# lcd_key_led.net
KiCad netlist of a schematic drawn in Altium Designer
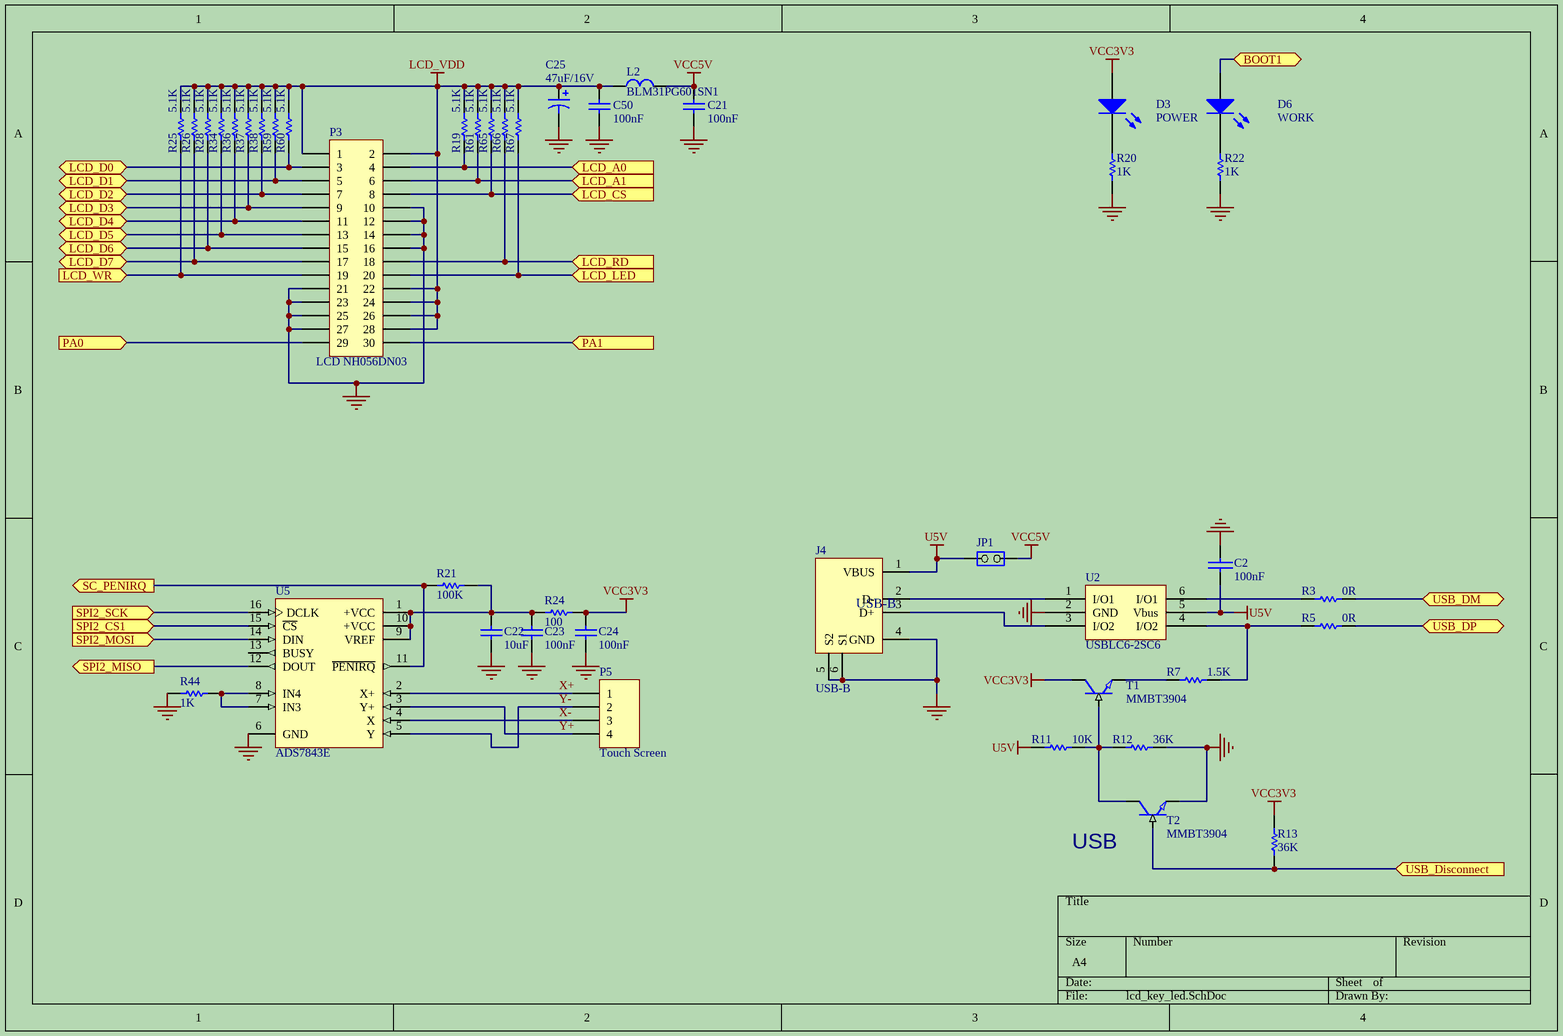
[diagram p0: lcd_key_led.SchDoc]

(export (version "E")
  (design (tool "Eeschema 10.0.6"))
  (components
    (comp (ref "C2")
      (value "100nF")
      (footprint "C0805")
      (description "Capacitor")
      (libsource (lib "*") (part "CAP"))
    )
    (comp (ref "C21")
      (value "100nF")
      (footprint "C0805")
      (description "Capacitor")
      (fields (field (name "PUBLISHER") "Altium Limited"))
      (libsource (lib "Miscellaneous Devices") (part "CAP"))
    )
    (comp (ref "C22")
      (value "10uF")
      (footprint "C1206")
      (description "Capacitor")
      (fields (field (name "PUBLISHER") "Altium Limited"))
      (libsource (lib "Miscellaneous Devices") (part "CAP"))
    )
    (comp (ref "C23")
      (value "100nF")
      (footprint "C0805")
      (description "Capacitor")
      (fields (field (name "PUBLISHER") "Altium Limited"))
      (libsource (lib "Miscellaneous Devices") (part "CAP"))
    )
    (comp (ref "C24")
      (value "100nF")
      (footprint "C0805")
      (description "Capacitor")
      (fields (field (name "PUBLISHER") "Altium Limited"))
      (libsource (lib "Miscellaneous Devices") (part "CAP"))
    )
    (comp (ref "C25")
      (value "47uF/16V")
      (footprint "CD1/2")
      (description "Polarized Capacitor (Radial)")
      (fields (field (name "PUBLISHER") "Altium Limited"))
      (libsource (lib "Miscellaneous Devices") (part "Cap Pol1"))
    )
    (comp (ref "C50")
      (value "100nF")
      (footprint "C0805")
      (description "Capacitor")
      (fields (field (name "PUBLISHER") "Altium Limited"))
      (libsource (lib "Miscellaneous Devices") (part "CAP"))
    )
    (comp (ref "D3")
      (value "POWER")
      (footprint "LED0805")
      (description "Typical INFRARED GaAs LED")
      (fields (field (name "PUBLISHER") "Altium Limited"))
      (libsource (lib "Miscellaneous Devices") (part "LED0"))
    )
    (comp (ref "D6")
      (value "WORK")
      (footprint "LED0805")
      (description "Typical INFRARED GaAs LED")
      (fields (field (name "PUBLISHER") "Altium Limited"))
      (libsource (lib "Miscellaneous Devices") (part "LED0"))
    )
    (comp (ref "J4") (value "USB-B") (footprint "USB-B") (libsource (lib "Devices") (part "USB-B")))
    (comp (ref "JP1") (value "~") (footprint "SIP2") (libsource (lib "*") (part "JP2")))
    (comp (ref "L2") (value "BLM31PG601SN1") (footprint "l1206") (libsource (lib "Devices") (part "L1")))
    (comp (ref "P3")
      (value "LCD NH056DN03")
      (footprint "HDR2X15")
      (description "Header, 15-Pin, Dual row")
      (fields (field (name "PUBLISHER") "Altium Limited"))
      (libsource (lib "Miscellaneous Connectors") (part "Header 15X2"))
    )
    (comp (ref "P5")
      (value "Touch Screen")
      (footprint "TJC3-4A")
      (description "Header, 4-Pin")
      (fields (field (name "PUBLISHER") "Altium Limited"))
      (libsource (lib "Miscellaneous Connectors") (part "Header 4"))
    )
    (comp (ref "R3")
      (value "0R")
      (footprint "R0805")
      (description "Resistor")
      (fields (field (name "PUBLISHER") "Altium Limited"))
      (libsource (lib "") (part "Res1_1"))
    )
    (comp (ref "R5")
      (value "0R")
      (footprint "R0805")
      (description "Resistor")
      (fields (field (name "PUBLISHER") "Altium Limited"))
      (libsource (lib "") (part "Res1_1"))
    )
    (comp (ref "R7")
      (value "1.5K")
      (footprint "R0805")
      (description "Resistor")
      (fields (field (name "PUBLISHER") "Altium Limited"))
      (libsource (lib "") (part "Res1_1"))
    )
    (comp (ref "R11")
      (value "10K")
      (footprint "R0805")
      (description "Resistor")
      (fields (field (name "PUBLISHER") "Altium Limited"))
      (libsource (lib "") (part "Res1_1"))
    )
    (comp (ref "R12")
      (value "36K")
      (footprint "R0805")
      (description "Resistor")
      (fields (field (name "PUBLISHER") "Altium Limited"))
      (libsource (lib "") (part "Res1_1"))
    )
    (comp (ref "R13")
      (value "36K")
      (footprint "R0805")
      (description "Resistor")
      (fields (field (name "PUBLISHER") "Altium Limited"))
      (libsource (lib "") (part "Res1_1"))
    )
    (comp (ref "R19")
      (value "5.1K")
      (footprint "R0805")
      (description "Resistor")
      (fields (field (name "PUBLISHER") "Altium Limited"))
      (libsource (lib "Miscellaneous Devices") (part "Res1"))
    )
    (comp (ref "R20")
      (value "1K")
      (footprint "R0805")
      (description "Resistor")
      (fields (field (name "PUBLISHER") "Altium Limited"))
      (libsource (lib "Miscellaneous Devices") (part "Res1"))
    )
    (comp (ref "R21")
      (value "100K")
      (footprint "R0805")
      (description "Resistor")
      (fields (field (name "PUBLISHER") "Altium Limited"))
      (libsource (lib "Miscellaneous Devices") (part "Res1"))
    )
    (comp (ref "R22")
      (value "1K")
      (footprint "R0805")
      (description "Resistor")
      (fields (field (name "PUBLISHER") "Altium Limited"))
      (libsource (lib "Miscellaneous Devices") (part "Res1"))
    )
    (comp (ref "R24")
      (value "100")
      (footprint "R0805")
      (description "Resistor")
      (fields (field (name "PUBLISHER") "Altium Limited"))
      (libsource (lib "Miscellaneous Devices") (part "Res1"))
    )
    (comp (ref "R25")
      (value "5.1K")
      (footprint "R0805")
      (description "Resistor")
      (fields (field (name "PUBLISHER") "Altium Limited"))
      (libsource (lib "Miscellaneous Devices") (part "Res1"))
    )
    (comp (ref "R26")
      (value "5.1K")
      (footprint "R0805")
      (description "Resistor")
      (fields (field (name "PUBLISHER") "Altium Limited"))
      (libsource (lib "Miscellaneous Devices") (part "Res1"))
    )
    (comp (ref "R28")
      (value "5.1K")
      (footprint "R0805")
      (description "Resistor")
      (fields (field (name "PUBLISHER") "Altium Limited"))
      (libsource (lib "Miscellaneous Devices") (part "Res1"))
    )
    (comp (ref "R34")
      (value "5.1K")
      (footprint "R0805")
      (description "Resistor")
      (fields (field (name "PUBLISHER") "Altium Limited"))
      (libsource (lib "Miscellaneous Devices") (part "Res1"))
    )
    (comp (ref "R36")
      (value "5.1K")
      (footprint "R0805")
      (description "Resistor")
      (fields (field (name "PUBLISHER") "Altium Limited"))
      (libsource (lib "Miscellaneous Devices") (part "Res1"))
    )
    (comp (ref "R37")
      (value "5.1K")
      (footprint "R0805")
      (description "Resistor")
      (fields (field (name "PUBLISHER") "Altium Limited"))
      (libsource (lib "Miscellaneous Devices") (part "Res1"))
    )
    (comp (ref "R38")
      (value "5.1K")
      (footprint "R0805")
      (description "Resistor")
      (fields (field (name "PUBLISHER") "Altium Limited"))
      (libsource (lib "Miscellaneous Devices") (part "Res1"))
    )
    (comp (ref "R44")
      (value "1K")
      (footprint "R0805")
      (description "Resistor")
      (fields (field (name "PUBLISHER") "Altium Limited"))
      (libsource (lib "Miscellaneous Devices") (part "Res1"))
    )
    (comp (ref "R59")
      (value "5.1K")
      (footprint "R0805")
      (description "Resistor")
      (fields (field (name "PUBLISHER") "Altium Limited"))
      (libsource (lib "Miscellaneous Devices") (part "Res1"))
    )
    (comp (ref "R60")
      (value "5.1K")
      (footprint "R0805")
      (description "Resistor")
      (fields (field (name "PUBLISHER") "Altium Limited"))
      (libsource (lib "Miscellaneous Devices") (part "Res1"))
    )
    (comp (ref "R61")
      (value "5.1K")
      (footprint "R0805")
      (description "Resistor")
      (fields (field (name "PUBLISHER") "Altium Limited"))
      (libsource (lib "Miscellaneous Devices") (part "Res1"))
    )
    (comp (ref "R65")
      (value "5.1K")
      (footprint "R0805")
      (description "Resistor")
      (fields (field (name "PUBLISHER") "Altium Limited"))
      (libsource (lib "Miscellaneous Devices") (part "Res1"))
    )
    (comp (ref "R66")
      (value "5.1K")
      (footprint "R0805")
      (description "Resistor")
      (fields (field (name "PUBLISHER") "Altium Limited"))
      (libsource (lib "Miscellaneous Devices") (part "Res1"))
    )
    (comp (ref "R67")
      (value "5.1K")
      (footprint "R0805")
      (description "Resistor")
      (fields (field (name "PUBLISHER") "Altium Limited"))
      (libsource (lib "Miscellaneous Devices") (part "Res1"))
    )
    (comp (ref "T1") (value "MMBT3904") (footprint "SOT-23") (libsource (lib "Devices") (part "NPN_SOT23")))
    (comp (ref "T2") (value "MMBT3904") (footprint "SOT-23") (libsource (lib "Devices") (part "NPN_SOT23")))
    (comp (ref "U2")
      (value "USBLC6-2SC6")
      (footprint "SOT-23/6")
      (libsource (lib "STR910_SCHLIB") (part "USBLC6-2"))
    )
    (comp (ref "U5")
      (value "ADS7843E")
      (footprint "DBQ016")
      (description "4-Wire Touch Screen Controller, 16-Pin SSOP, Pb-Free")
      (fields (field (name "PUBLISHER") "Altium Limited"))
      (libsource (lib "TI Interface Touch Screen Controller") (part "ADS7843E"))
    )
  )
  (nets
    (net (code "1") (name "/BOOT1") (class "Default")
      (node (ref "D6") (pin "1") (pinfunction "A_1") (pintype "passive"))
    )
    (net (code "2") (name "/LCD_A0") (class "Default")
      (node (ref "P3") (pin "4") (pinfunction "4_4") (pintype "passive"))
      (node (ref "R19") (pin "2") (pinfunction "2_2") (pintype "passive"))
    )
    (net (code "3") (name "/LCD_A1") (class "Default")
      (node (ref "P3") (pin "6") (pinfunction "6_6") (pintype "passive"))
      (node (ref "R61") (pin "2") (pinfunction "2_2") (pintype "passive"))
    )
    (net (code "4") (name "/LCD_CS") (class "Default")
      (node (ref "P3") (pin "8") (pinfunction "8_8") (pintype "passive"))
      (node (ref "R65") (pin "2") (pinfunction "2_2") (pintype "passive"))
    )
    (net (code "5") (name "/LCD_D0") (class "Default")
      (node (ref "P3") (pin "3") (pinfunction "3_3") (pintype "passive"))
      (node (ref "R60") (pin "2") (pinfunction "2_2") (pintype "passive"))
    )
    (net (code "6") (name "/LCD_D1") (class "Default")
      (node (ref "P3") (pin "5") (pinfunction "5_5") (pintype "passive"))
      (node (ref "R59") (pin "2") (pinfunction "2_2") (pintype "passive"))
    )
    (net (code "7") (name "/LCD_D2") (class "Default")
      (node (ref "P3") (pin "7") (pinfunction "7_7") (pintype "passive"))
      (node (ref "R38") (pin "2") (pinfunction "2_2") (pintype "passive"))
    )
    (net (code "8") (name "/LCD_D3") (class "Default")
      (node (ref "P3") (pin "9") (pinfunction "9_9") (pintype "passive"))
      (node (ref "R37") (pin "2") (pinfunction "2_2") (pintype "passive"))
    )
    (net (code "9") (name "/LCD_D4") (class "Default")
      (node (ref "P3") (pin "11") (pinfunction "11_11") (pintype "passive"))
      (node (ref "R36") (pin "2") (pinfunction "2_2") (pintype "passive"))
    )
    (net (code "10") (name "/LCD_D5") (class "Default")
      (node (ref "P3") (pin "13") (pinfunction "13_13") (pintype "passive"))
      (node (ref "R34") (pin "2") (pinfunction "2_2") (pintype "passive"))
    )
    (net (code "11") (name "/LCD_D6") (class "Default")
      (node (ref "P3") (pin "15") (pinfunction "15_15") (pintype "passive"))
      (node (ref "R28") (pin "2") (pinfunction "2_2") (pintype "passive"))
    )
    (net (code "12") (name "/LCD_D7") (class "Default")
      (node (ref "P3") (pin "17") (pinfunction "17_17") (pintype "passive"))
      (node (ref "R26") (pin "2") (pinfunction "2_2") (pintype "passive"))
    )
    (net (code "13") (name "/LCD_LED") (class "Default")
      (node (ref "P3") (pin "20") (pinfunction "20_20") (pintype "passive"))
      (node (ref "R67") (pin "2") (pinfunction "2_2") (pintype "passive"))
    )
    (net (code "14") (name "/LCD_RD") (class "Default")
      (node (ref "P3") (pin "18") (pinfunction "18_18") (pintype "passive"))
      (node (ref "R66") (pin "2") (pinfunction "2_2") (pintype "passive"))
    )
    (net (code "15") (name "/LCD_WR") (class "Default")
      (node (ref "P3") (pin "19") (pinfunction "19_19") (pintype "passive"))
      (node (ref "R25") (pin "2") (pinfunction "2_2") (pintype "passive"))
    )
    (net (code "16") (name "/PA0") (class "Default")
      (node (ref "P3") (pin "29") (pinfunction "29_29") (pintype "passive"))
    )
    (net (code "17") (name "/PA1") (class "Default")
      (node (ref "P3") (pin "30") (pinfunction "30_30") (pintype "passive"))
    )
    (net (code "18") (name "/SC_PENIRQ") (class "Default")
      (node (ref "R21") (pin "1") (pinfunction "1_1") (pintype "passive"))
      (node (ref "U5") (pin "11") (pinfunction "~{PENIRQ}_11") (pintype "output"))
    )
    (net (code "19") (name "/SPI2_CS1") (class "Default")
      (node (ref "U5") (pin "15") (pinfunction "~{CS}_15") (pintype "input"))
    )
    (net (code "20") (name "/SPI2_MISO") (class "Default")
      (node (ref "U5") (pin "12") (pinfunction "DOUT_12") (pintype "output"))
    )
    (net (code "21") (name "/SPI2_MOSI") (class "Default")
      (node (ref "U5") (pin "14") (pinfunction "DIN_14") (pintype "input"))
    )
    (net (code "22") (name "/SPI2_SCK") (class "Default")
      (node (ref "U5") (pin "16") (pinfunction "DCLK_16") (pintype "input"))
    )
    (net (code "23") (name "/USB_DM") (class "Default")
      (node (ref "R3") (pin "1") (pinfunction "1_1") (pintype "passive"))
    )
    (net (code "24") (name "/USB_DP") (class "Default")
      (node (ref "R5") (pin "1") (pinfunction "1_1") (pintype "passive"))
    )
    (net (code "25") (name "/USB_Disconnect") (class "Default")
      (node (ref "R13") (pin "1") (pinfunction "1_1") (pintype "passive"))
      (node (ref "T2") (pin "1") (pinfunction "B_1") (pintype "input"))
    )
    (net (code "26") (name "/X+") (class "Default")
      (node (ref "P5") (pin "1") (pinfunction "1_1") (pintype "passive"))
      (node (ref "U5") (pin "2") (pinfunction "X+_2") (pintype "input"))
    )
    (net (code "27") (name "/X-") (class "Default")
      (node (ref "P5") (pin "3") (pinfunction "3_3") (pintype "passive"))
      (node (ref "U5") (pin "4") (pinfunction "X_4") (pintype "input"))
    )
    (net (code "28") (name "/Y+") (class "Default")
      (node (ref "P5") (pin "4") (pinfunction "4_4") (pintype "passive"))
      (node (ref "U5") (pin "3") (pinfunction "Y+_3") (pintype "input"))
    )
    (net (code "29") (name "/Y-") (class "Default")
      (node (ref "P5") (pin "2") (pinfunction "2_2") (pintype "passive"))
      (node (ref "U5") (pin "5") (pinfunction "Y_5") (pintype "input"))
    )
    (net (code "30") (name "GND") (class "Default")
      (node (ref "C2") (pin "1") (pinfunction "1_1") (pintype "passive"))
      (node (ref "C21") (pin "1") (pinfunction "1_1") (pintype "passive"))
      (node (ref "C22") (pin "1") (pinfunction "1_1") (pintype "passive"))
      (node (ref "C23") (pin "1") (pinfunction "1_1") (pintype "passive"))
      (node (ref "C24") (pin "1") (pinfunction "1_1") (pintype "passive"))
      (node (ref "C25") (pin "2") (pinfunction "2_2") (pintype "passive"))
      (node (ref "C50") (pin "1") (pinfunction "1_1") (pintype "passive"))
      (node (ref "J4") (pin "4") (pinfunction "GND_4") (pintype "passive"))
      (node (ref "J4") (pin "5") (pinfunction "S2_5") (pintype "passive"))
      (node (ref "J4") (pin "6") (pinfunction "S1_6") (pintype "passive"))
      (node (ref "P3") (pin "10") (pinfunction "10_10") (pintype "passive"))
      (node (ref "P3") (pin "12") (pinfunction "12_12") (pintype "passive"))
      (node (ref "P3") (pin "14") (pinfunction "14_14") (pintype "passive"))
      (node (ref "P3") (pin "16") (pinfunction "16_16") (pintype "passive"))
      (node (ref "P3") (pin "21") (pinfunction "21_21") (pintype "passive"))
      (node (ref "P3") (pin "23") (pinfunction "23_23") (pintype "passive"))
      (node (ref "P3") (pin "25") (pinfunction "25_25") (pintype "passive"))
      (node (ref "P3") (pin "27") (pinfunction "27_27") (pintype "passive"))
      (node (ref "R12") (pin "1") (pinfunction "1_1") (pintype "passive"))
      (node (ref "R20") (pin "2") (pinfunction "2_2") (pintype "passive"))
      (node (ref "R22") (pin "2") (pinfunction "2_2") (pintype "passive"))
      (node (ref "R44") (pin "1") (pinfunction "1_1") (pintype "passive"))
      (node (ref "T2") (pin "2") (pinfunction "E_2") (pintype "open_emitter"))
      (node (ref "U2") (pin "2") (pinfunction "GND_2") (pintype "passive"))
      (node (ref "U5") (pin "6") (pinfunction "GND_6") (pintype "power_in"))
    )
    (net (code "31") (name "LCD_VDD") (class "Default")
      (node (ref "C25") (pin "1") (pinfunction "1_1") (pintype "passive"))
      (node (ref "C50") (pin "2") (pinfunction "2_2") (pintype "passive"))
      (node (ref "L2") (pin "1") (pinfunction "1_1") (pintype "passive"))
      (node (ref "P3") (pin "1") (pinfunction "1_1") (pintype "passive"))
      (node (ref "P3") (pin "2") (pinfunction "2_2") (pintype "passive"))
      (node (ref "P3") (pin "22") (pinfunction "22_22") (pintype "passive"))
      (node (ref "P3") (pin "24") (pinfunction "24_24") (pintype "passive"))
      (node (ref "P3") (pin "26") (pinfunction "26_26") (pintype "passive"))
      (node (ref "P3") (pin "28") (pinfunction "28_28") (pintype "passive"))
      (node (ref "R19") (pin "1") (pinfunction "1_1") (pintype "passive"))
      (node (ref "R25") (pin "1") (pinfunction "1_1") (pintype "passive"))
      (node (ref "R26") (pin "1") (pinfunction "1_1") (pintype "passive"))
      (node (ref "R28") (pin "1") (pinfunction "1_1") (pintype "passive"))
      (node (ref "R34") (pin "1") (pinfunction "1_1") (pintype "passive"))
      (node (ref "R36") (pin "1") (pinfunction "1_1") (pintype "passive"))
      (node (ref "R37") (pin "1") (pinfunction "1_1") (pintype "passive"))
      (node (ref "R38") (pin "1") (pinfunction "1_1") (pintype "passive"))
      (node (ref "R59") (pin "1") (pinfunction "1_1") (pintype "passive"))
      (node (ref "R60") (pin "1") (pinfunction "1_1") (pintype "passive"))
      (node (ref "R61") (pin "1") (pinfunction "1_1") (pintype "passive"))
      (node (ref "R65") (pin "1") (pinfunction "1_1") (pintype "passive"))
      (node (ref "R66") (pin "1") (pinfunction "1_1") (pintype "passive"))
      (node (ref "R67") (pin "1") (pinfunction "1_1") (pintype "passive"))
    )
    (net (code "32") (name "Net-(D3-K)") (class "Default")
      (node (ref "D3") (pin "2") (pinfunction "K_2") (pintype "passive"))
      (node (ref "R20") (pin "1") (pinfunction "1_1") (pintype "passive"))
    )
    (net (code "33") (name "Net-(D6-K)") (class "Default")
      (node (ref "D6") (pin "2") (pinfunction "K_2") (pintype "passive"))
      (node (ref "R22") (pin "1") (pinfunction "1_1") (pintype "passive"))
    )
    (net (code "34") (name "Net-(J4-D+)") (class "Default")
      (node (ref "J4") (pin "3") (pinfunction "D+_3") (pintype "passive"))
      (node (ref "U2") (pin "3") (pinfunction "I/O2_3") (pintype "passive"))
    )
    (net (code "35") (name "Net-(J4-D-)") (class "Default")
      (node (ref "J4") (pin "2") (pinfunction "D-_2") (pintype "passive"))
      (node (ref "U2") (pin "1") (pinfunction "I/O1_1") (pintype "passive"))
    )
    (net (code "36") (name "Net-(R3-Pad2)") (class "Default")
      (node (ref "R3") (pin "2") (pinfunction "2_2") (pintype "passive"))
      (node (ref "U2") (pin "6") (pinfunction "I/O1_6") (pintype "passive"))
    )
    (net (code "37") (name "Net-(R5-Pad2)") (class "Default")
      (node (ref "R5") (pin "2") (pinfunction "2_2") (pintype "passive"))
      (node (ref "R7") (pin "1") (pinfunction "1_1") (pintype "passive"))
      (node (ref "U2") (pin "4") (pinfunction "I/O2_4") (pintype "passive"))
    )
    (net (code "38") (name "Net-(T1-B)") (class "Default")
      (node (ref "R11") (pin "1") (pinfunction "1_1") (pintype "passive"))
      (node (ref "R12") (pin "2") (pinfunction "2_2") (pintype "passive"))
      (node (ref "T1") (pin "1") (pinfunction "B_1") (pintype "input"))
      (node (ref "T2") (pin "3") (pinfunction "C_3") (pintype "open_collector"))
    )
    (net (code "39") (name "Net-(T1-E)") (class "Default")
      (node (ref "R7") (pin "2") (pinfunction "2_2") (pintype "passive"))
      (node (ref "T1") (pin "2") (pinfunction "E_2") (pintype "open_emitter"))
    )
    (net (code "40") (name "Net-(U5-IN3)") (class "Default")
      (node (ref "R44") (pin "2") (pinfunction "2_2") (pintype "passive"))
      (node (ref "U5") (pin "7") (pinfunction "IN3_7") (pintype "input"))
      (node (ref "U5") (pin "8") (pinfunction "IN4_8") (pintype "input"))
    )
    (net (code "41") (name "Net-(U5-VREF)") (class "Default")
      (node (ref "C22") (pin "2") (pinfunction "2_2") (pintype "passive"))
      (node (ref "C23") (pin "2") (pinfunction "2_2") (pintype "passive"))
      (node (ref "R21") (pin "2") (pinfunction "2_2") (pintype "passive"))
      (node (ref "R24") (pin "1") (pinfunction "1_1") (pintype "passive"))
      (node (ref "U5") (pin "1") (pinfunction "+VCC_1") (pintype "power_in"))
      (node (ref "U5") (pin "10") (pinfunction "+VCC_10") (pintype "power_in"))
      (node (ref "U5") (pin "9") (pinfunction "VREF_9") (pintype "power_in"))
    )
    (net (code "42") (name "U5V") (class "Default")
      (node (ref "C2") (pin "2") (pinfunction "2_2") (pintype "passive"))
      (node (ref "J4") (pin "1") (pinfunction "VBUS_1") (pintype "passive"))
      (node (ref "JP1") (pin "2") (pinfunction "NO_2") (pintype "passive"))
      (node (ref "R11") (pin "2") (pinfunction "2_2") (pintype "passive"))
      (node (ref "U2") (pin "5") (pinfunction "Vbus_5") (pintype "passive"))
    )
    (net (code "43") (name "VCC3V3") (class "Default")
      (node (ref "C24") (pin "2") (pinfunction "2_2") (pintype "passive"))
      (node (ref "D3") (pin "1") (pinfunction "A_1") (pintype "passive"))
      (node (ref "R13") (pin "2") (pinfunction "2_2") (pintype "passive"))
      (node (ref "R24") (pin "2") (pinfunction "2_2") (pintype "passive"))
      (node (ref "T1") (pin "3") (pinfunction "C_3") (pintype "open_collector"))
    )
    (net (code "44") (name "VCC5V") (class "Default")
      (node (ref "C21") (pin "2") (pinfunction "2_2") (pintype "passive"))
      (node (ref "JP1") (pin "1") (pinfunction "COMMON_1") (pintype "passive"))
      (node (ref "L2") (pin "2") (pinfunction "2_2") (pintype "passive"))
    )
    (net (code "45") (name "unconnected-(U5-BUSY-Pad13)") (class "Default")
      (node (ref "U5") (pin "13") (pinfunction "BUSY_13") (pintype "output"))
    )
  )
)
